# STM32_Trans_sheet.net
KiCad netlist of a schematic drawn in Altium Designer
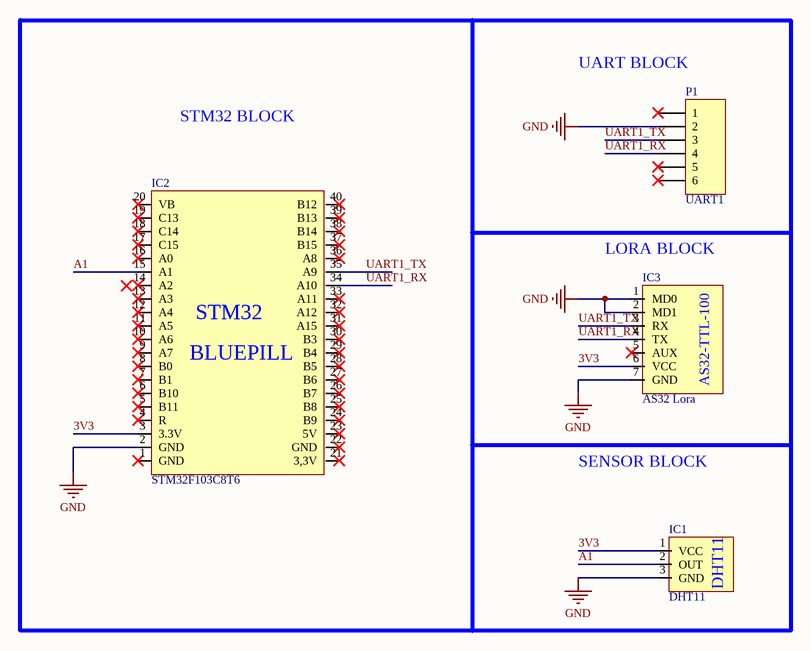
[diagram p0: STM32_Trans_sheet.SchDoc]

(export (version "E")
  (design (tool "Eeschema 10.0.6"))
  (components
    (comp (ref "IC1") (value "DHT11") (footprint "DHT11") (libsource (lib "Lib_Inter") (part "DHT11")))
    (comp (ref "IC2")
      (value "STM32F103C8T6")
      (footprint "STM32_BLUEPILL")
      (libsource (lib "Lib_Inter") (part "STM32_BLUEPILL"))
    )
    (comp (ref "IC3") (value "AS32 Lora") (footprint "LORA") (libsource (lib "Lib_Inter") (part "LORA")))
    (comp (ref "P1")
      (value "UART1")
      (footprint "HDR1X6")
      (description "Header, 6-Pin")
      (fields (field (name "PUBLISHER") "Altium Limited"))
      (libsource (lib "Library AL") (part "Header 6"))
    )
  )
  (nets
    (net (code "1") (name "/3V3") (class "Default")
      (node (ref "IC1") (pin "1") (pinfunction "VCC_1") (pintype "passive"))
      (node (ref "IC2") (pin "3") (pinfunction "3.3V_3") (pintype "passive"))
      (node (ref "IC3") (pin "6") (pinfunction "VCC_6") (pintype "passive"))
    )
    (net (code "2") (name "/A1") (class "Default")
      (node (ref "IC1") (pin "2") (pinfunction "OUT_2") (pintype "passive"))
      (node (ref "IC2") (pin "15") (pinfunction "A1_15") (pintype "passive"))
    )
    (net (code "3") (name "/UART1_RX") (class "Default")
      (node (ref "IC2") (pin "34") (pinfunction "A10_34") (pintype "passive"))
      (node (ref "IC3") (pin "4") (pinfunction "TX_4") (pintype "passive"))
      (node (ref "P1") (pin "4") (pinfunction "4_4") (pintype "passive"))
    )
    (net (code "4") (name "/UART1_TX") (class "Default")
      (node (ref "IC2") (pin "35") (pinfunction "A9_35") (pintype "passive"))
      (node (ref "IC3") (pin "3") (pinfunction "RX_3") (pintype "passive"))
      (node (ref "P1") (pin "3") (pinfunction "3_3") (pintype "passive"))
    )
    (net (code "5") (name "GND") (class "Default")
      (node (ref "IC1") (pin "3") (pinfunction "GND_3") (pintype "passive"))
      (node (ref "IC2") (pin "2") (pinfunction "GND_2") (pintype "passive"))
      (node (ref "IC3") (pin "1") (pinfunction "MD0_1") (pintype "passive"))
      (node (ref "IC3") (pin "2") (pinfunction "MD1_2") (pintype "passive"))
      (node (ref "IC3") (pin "7") (pinfunction "GND_7") (pintype "passive"))
      (node (ref "P1") (pin "2") (pinfunction "2_2") (pintype "passive"))
    )
    (net (code "6") (name "unconnected-(IC2-3,3V-Pad21)") (class "Default")
      (node (ref "IC2") (pin "21") (pinfunction "3,3V_21") (pintype "passive+no_connect"))
    )
    (net (code "7") (name "unconnected-(IC2-5V-Pad23)") (class "Default")
      (node (ref "IC2") (pin "23") (pinfunction "5V_23") (pintype "passive+no_connect"))
    )
    (net (code "8") (name "unconnected-(IC2-A0-Pad16)") (class "Default")
      (node (ref "IC2") (pin "16") (pinfunction "A0_16") (pintype "passive+no_connect"))
    )
    (net (code "9") (name "unconnected-(IC2-A2-Pad14)") (class "Default")
      (node (ref "IC2") (pin "14") (pinfunction "A2_14") (pintype "passive+no_connect"))
    )
    (net (code "10") (name "unconnected-(IC2-A3-Pad13)") (class "Default")
      (node (ref "IC2") (pin "13") (pinfunction "A3_13") (pintype "passive+no_connect"))
    )
    (net (code "11") (name "unconnected-(IC2-A4-Pad12)") (class "Default")
      (node (ref "IC2") (pin "12") (pinfunction "A4_12") (pintype "passive+no_connect"))
    )
    (net (code "12") (name "unconnected-(IC2-A5-Pad11)") (class "Default")
      (node (ref "IC2") (pin "11") (pinfunction "A5_11") (pintype "passive+no_connect"))
    )
    (net (code "13") (name "unconnected-(IC2-A6-Pad10)") (class "Default")
      (node (ref "IC2") (pin "10") (pinfunction "A6_10") (pintype "passive+no_connect"))
    )
    (net (code "14") (name "unconnected-(IC2-A7-Pad9)") (class "Default")
      (node (ref "IC2") (pin "9") (pinfunction "A7_9") (pintype "passive+no_connect"))
    )
    (net (code "15") (name "unconnected-(IC2-A8-Pad36)") (class "Default")
      (node (ref "IC2") (pin "36") (pinfunction "A8_36") (pintype "passive+no_connect"))
    )
    (net (code "16") (name "unconnected-(IC2-A11-Pad33)") (class "Default")
      (node (ref "IC2") (pin "33") (pinfunction "A11_33") (pintype "passive+no_connect"))
    )
    (net (code "17") (name "unconnected-(IC2-A12-Pad32)") (class "Default")
      (node (ref "IC2") (pin "32") (pinfunction "A12_32") (pintype "passive+no_connect"))
    )
    (net (code "18") (name "unconnected-(IC2-A15-Pad31)") (class "Default")
      (node (ref "IC2") (pin "31") (pinfunction "A15_31") (pintype "passive+no_connect"))
    )
    (net (code "19") (name "unconnected-(IC2-B0-Pad8)") (class "Default")
      (node (ref "IC2") (pin "8") (pinfunction "B0_8") (pintype "passive+no_connect"))
    )
    (net (code "20") (name "unconnected-(IC2-B1-Pad7)") (class "Default")
      (node (ref "IC2") (pin "7") (pinfunction "B1_7") (pintype "passive+no_connect"))
    )
    (net (code "21") (name "unconnected-(IC2-B3-Pad30)") (class "Default")
      (node (ref "IC2") (pin "30") (pinfunction "B3_30") (pintype "passive+no_connect"))
    )
    (net (code "22") (name "unconnected-(IC2-B4-Pad29)") (class "Default")
      (node (ref "IC2") (pin "29") (pinfunction "B4_29") (pintype "passive+no_connect"))
    )
    (net (code "23") (name "unconnected-(IC2-B5-Pad28)") (class "Default")
      (node (ref "IC2") (pin "28") (pinfunction "B5_28") (pintype "passive+no_connect"))
    )
    (net (code "24") (name "unconnected-(IC2-B6-Pad27)") (class "Default")
      (node (ref "IC2") (pin "27") (pinfunction "B6_27") (pintype "passive+no_connect"))
    )
    (net (code "25") (name "unconnected-(IC2-B7-Pad26)") (class "Default")
      (node (ref "IC2") (pin "26") (pinfunction "B7_26") (pintype "passive+no_connect"))
    )
    (net (code "26") (name "unconnected-(IC2-B8-Pad25)") (class "Default")
      (node (ref "IC2") (pin "25") (pinfunction "B8_25") (pintype "passive+no_connect"))
    )
    (net (code "27") (name "unconnected-(IC2-B9-Pad24)") (class "Default")
      (node (ref "IC2") (pin "24") (pinfunction "B9_24") (pintype "passive+no_connect"))
    )
    (net (code "28") (name "unconnected-(IC2-B10-Pad6)") (class "Default")
      (node (ref "IC2") (pin "6") (pinfunction "B10_6") (pintype "passive+no_connect"))
    )
    (net (code "29") (name "unconnected-(IC2-B11-Pad5)") (class "Default")
      (node (ref "IC2") (pin "5") (pinfunction "B11_5") (pintype "passive+no_connect"))
    )
    (net (code "30") (name "unconnected-(IC2-B12-Pad40)") (class "Default")
      (node (ref "IC2") (pin "40") (pinfunction "B12_40") (pintype "passive+no_connect"))
    )
    (net (code "31") (name "unconnected-(IC2-B13-Pad39)") (class "Default")
      (node (ref "IC2") (pin "39") (pinfunction "B13_39") (pintype "passive+no_connect"))
    )
    (net (code "32") (name "unconnected-(IC2-B14-Pad38)") (class "Default")
      (node (ref "IC2") (pin "38") (pinfunction "B14_38") (pintype "passive+no_connect"))
    )
    (net (code "33") (name "unconnected-(IC2-B15-Pad37)") (class "Default")
      (node (ref "IC2") (pin "37") (pinfunction "B15_37") (pintype "passive+no_connect"))
    )
    (net (code "34") (name "unconnected-(IC2-C13-Pad19)") (class "Default")
      (node (ref "IC2") (pin "19") (pinfunction "C13_19") (pintype "passive+no_connect"))
    )
    (net (code "35") (name "unconnected-(IC2-C14-Pad18)") (class "Default")
      (node (ref "IC2") (pin "18") (pinfunction "C14_18") (pintype "passive+no_connect"))
    )
    (net (code "36") (name "unconnected-(IC2-C15-Pad17)") (class "Default")
      (node (ref "IC2") (pin "17") (pinfunction "C15_17") (pintype "passive+no_connect"))
    )
    (net (code "37") (name "unconnected-(IC2-GND-Pad1)") (class "Default")
      (node (ref "IC2") (pin "1") (pinfunction "GND_1") (pintype "passive+no_connect"))
    )
    (net (code "38") (name "unconnected-(IC2-GND-Pad22)") (class "Default")
      (node (ref "IC2") (pin "22") (pinfunction "GND_22") (pintype "passive+no_connect"))
    )
    (net (code "39") (name "unconnected-(IC2-R-Pad4)") (class "Default")
      (node (ref "IC2") (pin "4") (pinfunction "R_4") (pintype "passive+no_connect"))
    )
    (net (code "40") (name "unconnected-(IC2-VB-Pad20)") (class "Default")
      (node (ref "IC2") (pin "20") (pinfunction "VB_20") (pintype "passive+no_connect"))
    )
    (net (code "41") (name "unconnected-(IC3-AUX-Pad5)") (class "Default")
      (node (ref "IC3") (pin "5") (pinfunction "AUX_5") (pintype "passive+no_connect"))
    )
    (net (code "42") (name "unconnected-(P1-Pad1)") (class "Default")
      (node (ref "P1") (pin "1") (pinfunction "1_1") (pintype "passive+no_connect"))
    )
    (net (code "43") (name "unconnected-(P1-Pad5)") (class "Default")
      (node (ref "P1") (pin "5") (pinfunction "5_5") (pintype "passive+no_connect"))
    )
    (net (code "44") (name "unconnected-(P1-Pad6)") (class "Default")
      (node (ref "P1") (pin "6") (pinfunction "6_6") (pintype "passive+no_connect"))
    )
  )
)
